# motor_Controller4.net
KiCad netlist of a schematic drawn in EAGLE
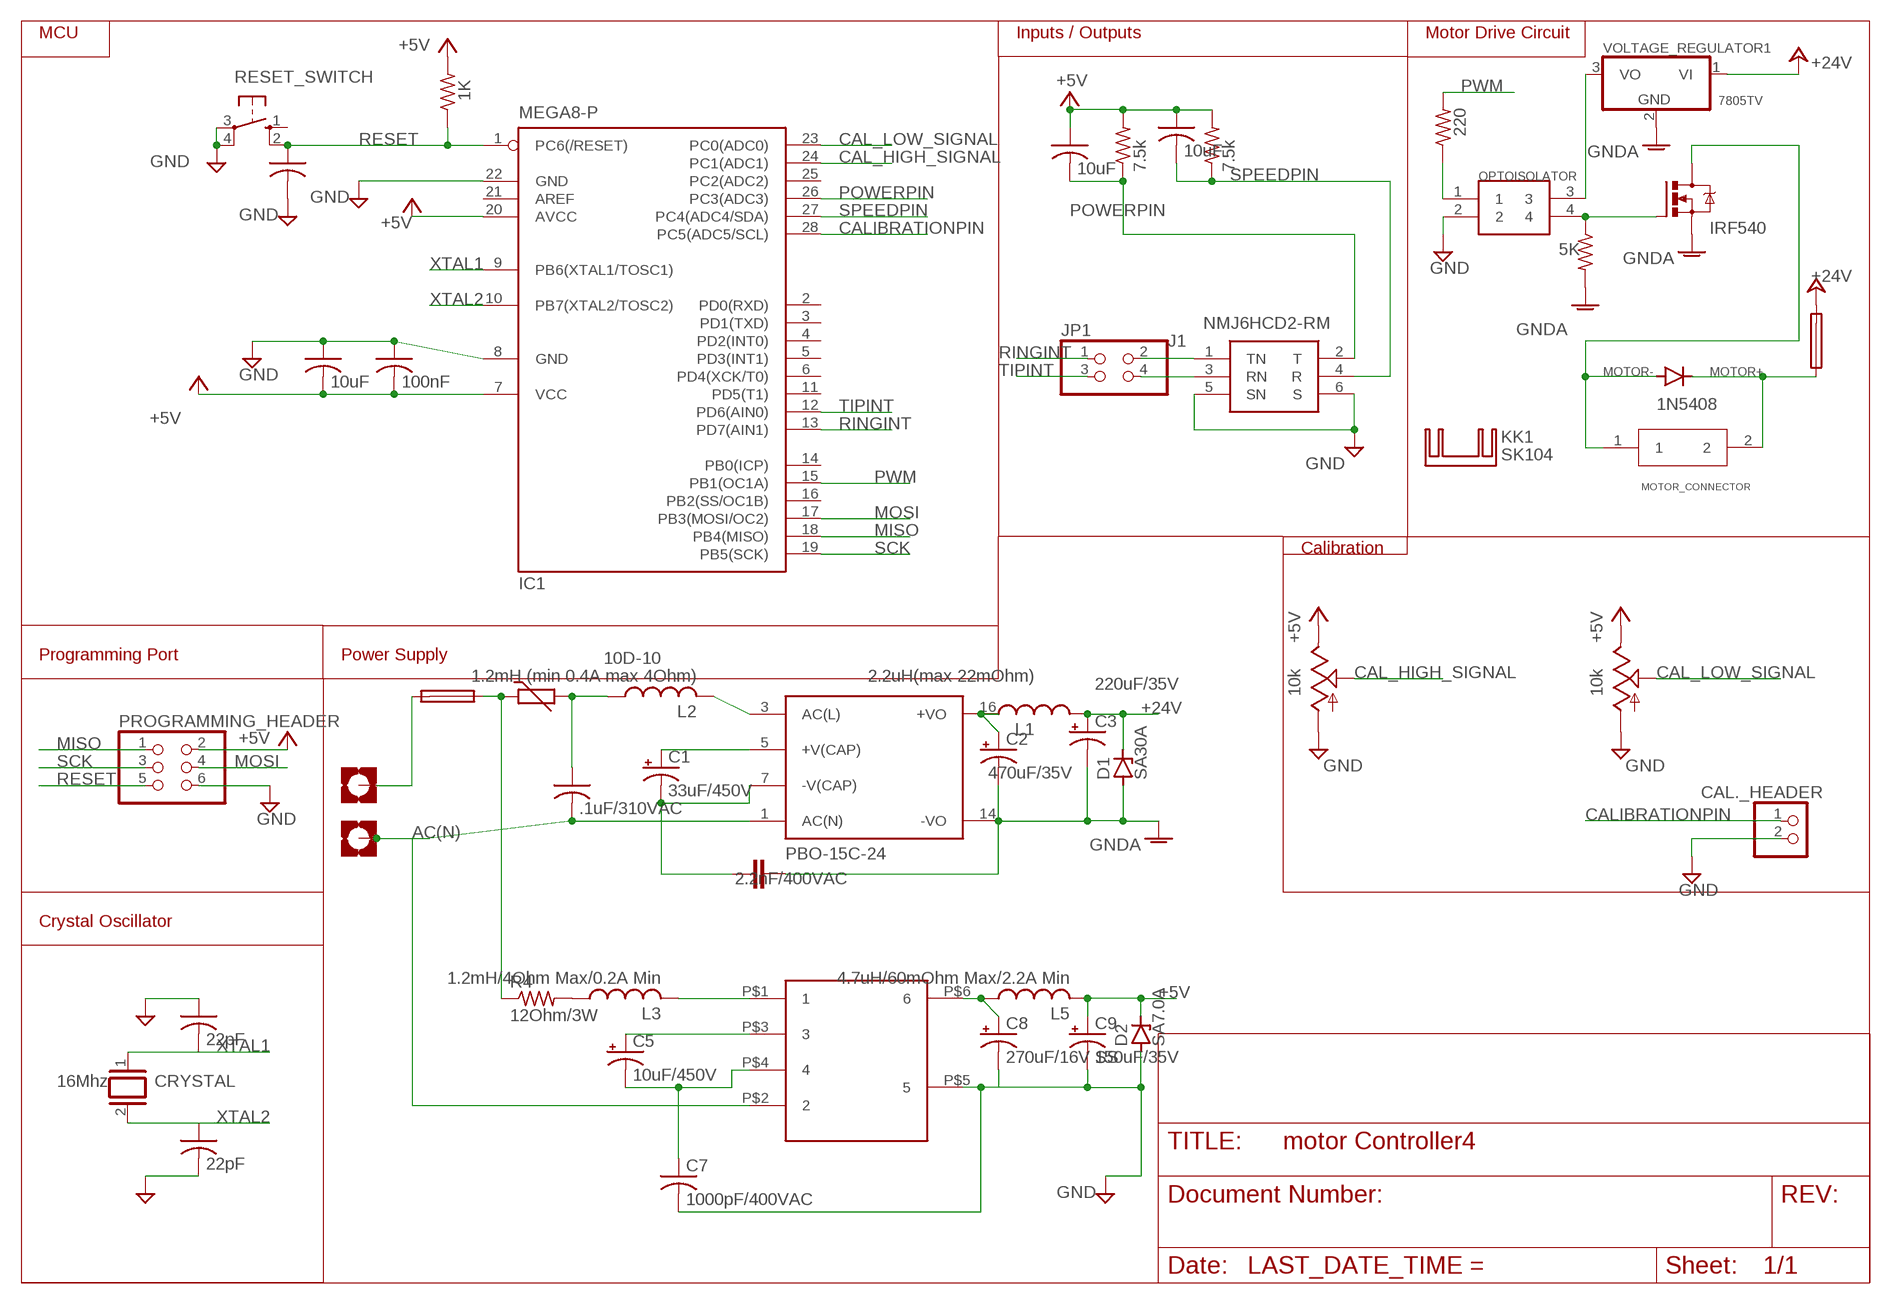
[diagram p0: schematic, sheet 1]

(export (version "E")
  (design (tool "Eeschema 10.0.6"))
  (components
    (comp (ref "1N5408")
      (value "1N5408")
      (footprint "eagle-import:DO201-15")
      (fields (field (name "MF") "VISHAY") (field (name "MPN") "1N5408-E3/54"))
      (libsource (lib "eagle-import") (part "1N5400"))
    )
    (comp (ref "C1")
      (value "33uF/450V")
      (footprint "eagle-import:E5-13")
      (libsource (lib "eagle-import") (part "CPOL-USE5-13"))
    )
    (comp (ref "C2")
      (value "470uF/35V")
      (footprint "eagle-import:E5-10,5")
      (fields (field (name "MF") "PANASONIC") (field (name "MPN") "ECA1VHG471B"))
      (libsource (lib "eagle-import") (part "CPOL-USE5-10.5"))
    )
    (comp (ref "C3")
      (value "220uF/35V")
      (footprint "eagle-import:E5-10,5")
      (fields (field (name "MF") "KEMET") (field (name "MPN") "A768KS227M1VLAE024"))
      (libsource (lib "eagle-import") (part "CPOL-USE5-10.5"))
    )
    (comp (ref "C4")
      (value ".1uF/310VAC")
      (footprint "eagle-import:C150-091X182")
      (libsource (lib "eagle-import") (part "C-US150-091X182"))
    )
    (comp (ref "C5")
      (value "10uF/450V")
      (footprint "eagle-import:E5-10,5")
      (libsource (lib "eagle-import") (part "CPOL-USE5-10.5"))
    )
    (comp (ref "C6")
      (value "22pF")
      (footprint "eagle-import:C025-024X044")
      (libsource (lib "eagle-import") (part "C-US025-024X044"))
    )
    (comp (ref "C7")
      (value "1000pF/400VAC")
      (footprint "eagle-import:C075-052X106")
      (libsource (lib "eagle-import") (part "C-US075-052X106"))
    )
    (comp (ref "C8")
      (value "270uF/16V SS")
      (footprint "eagle-import:E2,5-6")
      (libsource (lib "eagle-import") (part "CPOL-USE2.5-6"))
    )
    (comp (ref "C9")
      (value "150uF/35V")
      (footprint "eagle-import:E3,5-8")
      (libsource (lib "eagle-import") (part "CPOL-USE3.5-8"))
    )
    (comp (ref "C10")
      (value "10uF")
      (footprint "eagle-import:C025-024X044")
      (libsource (lib "eagle-import") (part "C-US025-024X044"))
    )
    (comp (ref "C11")
      (value "C-US025-024X044")
      (footprint "eagle-import:C025-024X044")
      (libsource (lib "eagle-import") (part "C-US025-024X044"))
    )
    (comp (ref "C12")
      (value "10uF")
      (footprint "eagle-import:C025-024X044")
      (libsource (lib "eagle-import") (part "C-US025-024X044"))
    )
    (comp (ref "C13")
      (value "10uF")
      (footprint "eagle-import:C025-024X044")
      (libsource (lib "eagle-import") (part "C-US025-024X044"))
    )
    (comp (ref "C14")
      (value "100nF")
      (footprint "eagle-import:C025-024X044")
      (libsource (lib "eagle-import") (part "C-US025-024X044"))
    )
    (comp (ref "C15")
      (value "22pF")
      (footprint "eagle-import:C025-024X044")
      (libsource (lib "eagle-import") (part "C-US025-024X044"))
    )
    (comp (ref "CAL._HEADER")
      (value "PINHD-1X2")
      (footprint "eagle-import:1X02")
      (libsource (lib "eagle-import") (part "PINHD-1X2"))
    )
    (comp (ref "CRYSTAL")
      (value "16Mhz")
      (footprint "eagle-import:QS")
      (libsource (lib "eagle-import") (part "XTAL/S"))
    )
    (comp (ref "CY1")
      (value "2.2nF/400VAC")
      (footprint "eagle-import:YC10B4")
      (libsource (lib "eagle-import") (part "CYYC10B4"))
    )
    (comp (ref "D1")
      (value "SA30A")
      (footprint "eagle-import:ZDIO-7.5")
      (libsource (lib "eagle-import") (part "ZENER-DIODEZD-7.5"))
    )
    (comp (ref "D2")
      (value "SA7.0A")
      (footprint "eagle-import:ZDIO-7.5")
      (libsource (lib "eagle-import") (part "ZENER-DIODEZD-7.5"))
    )
    (comp (ref "F1")
      (value "FUSESH22,5")
      (footprint "eagle-import:SH22,5")
      (libsource (lib "eagle-import") (part "FUSESH22,5"))
    )
    (comp (ref "F2")
      (value "1A/300V")
      (footprint "eagle-import:SH22,5")
      (libsource (lib "eagle-import") (part "FUSESH22,5"))
    )
    (comp (ref "FAST")
      (value "10k")
      (footprint "eagle-import:CT6")
      (libsource (lib "eagle-import") (part "TRIM_US-CT6"))
    )
    (comp (ref "H1")
      (value "MOUNT-PAD-SQUARE3.6")
      (footprint "eagle-import:3,6-PAD-SQUARE")
      (libsource (lib "eagle-import") (part "MOUNT-PAD-SQUARE3.6"))
    )
    (comp (ref "H2")
      (value "MOUNT-PAD-SQUARE3.6")
      (footprint "eagle-import:3,6-PAD-SQUARE")
      (libsource (lib "eagle-import") (part "MOUNT-PAD-SQUARE3.6"))
    )
    (comp (ref "IC1")
      (value "MEGA8-P")
      (footprint "eagle-import:DIL28-3")
      (libsource (lib "eagle-import") (part "MEGA8-P"))
    )
    (comp (ref "J1")
      (value "NMJ6HCD2-RM")
      (footprint "eagle-import:NMJ6HCD2RM")
      (fields (field (name "MOUSER_PART_NUMBER") "568-NMJ6HCD2-RM"))
      (libsource (lib "eagle-import") (part "NMJ6HCD2-RM"))
    )
    (comp (ref "JP1")
      (value "PINHD-2X2")
      (footprint "eagle-import:2X02")
      (libsource (lib "eagle-import") (part "PINHD-2X2"))
    )
    (comp (ref "KK1")
      (value "SK104")
      (footprint "eagle-import:SK104")
      (libsource (lib "eagle-import") (part "SK104"))
    )
    (comp (ref "L1")
      (value "2.2uH(max 22mOhm)")
      (footprint "eagle-import:TJ5-U1")
      (libsource (lib "eagle-import") (part "L-USTJ5-U1"))
    )
    (comp (ref "L2")
      (value "1.2mH (min 0.4A max 4Ohm)")
      (footprint "eagle-import:6000-XXXX-RC")
      (libsource (lib "eagle-import") (part "L-US6000-XXX-RC"))
    )
    (comp (ref "L3")
      (value "1.2mH/4Ohm Max/0.2A Min")
      (footprint "eagle-import:6000-XXXX-RC")
      (libsource (lib "eagle-import") (part "L-US6000-XXX-RC"))
    )
    (comp (ref "L5")
      (value "4.7uH/60mOhm Max/2.2A Min")
      (footprint "eagle-import:0207_2V")
      (libsource (lib "eagle-import") (part "L-US0207/2V"))
    )
    (comp (ref "MOTOR_CONNECTOR")
      (value "641963-1")
      (footprint "eagle-import:641963-1_TYC")
      (libsource (lib "eagle-import") (part "641963-1"))
    )
    (comp (ref "OPTOISOLATOR")
      (value "SFH619A")
      (footprint "eagle-import:SFH619A")
      (fields (field (name "OPTOISOLATOR") "SFH619A"))
      (libsource (lib "eagle-import") (part "SFH619A-ND"))
    )
    (comp (ref "PROGRAMMING_HEADER")
      (value "PINHD-2X3")
      (footprint "eagle-import:2X03")
      (libsource (lib "eagle-import") (part "PINHD-2X3"))
    )
    (comp (ref "PS1")
      (value "PBO-15C-24")
      (footprint "eagle-import:CONV_PBO-15C-24")
      (fields (field (name "MF") "CUI Inc."))
      (libsource (lib "eagle-import") (part "PBO-15C-24"))
    )
    (comp (ref "Q1")
      (value "IRF540")
      (footprint "eagle-import:TO220BV")
      (libsource (lib "eagle-import") (part "IRF540"))
    )
    (comp (ref "R1")
      (value "10D-10")
      (footprint "eagle-import:R-7,5")
      (libsource (lib "eagle-import") (part "THERMISTOR-7,5"))
    )
    (comp (ref "R2")
      (value "1K")
      (footprint "eagle-import:0204_7")
      (libsource (lib "eagle-import") (part "R-US_0204/7"))
    )
    (comp (ref "R3")
      (value "7.5k")
      (footprint "eagle-import:0204_7")
      (libsource (lib "eagle-import") (part "R-US_0204/7"))
    )
    (comp (ref "R4")
      (value "12Ohm/3W")
      (footprint "eagle-import:0617_22")
      (libsource (lib "eagle-import") (part "R-US_0617/22"))
    )
    (comp (ref "R5")
      (value "220")
      (footprint "eagle-import:0204_7")
      (libsource (lib "eagle-import") (part "R-US_0204/7"))
    )
    (comp (ref "R6")
      (value "5K")
      (footprint "eagle-import:0204_7")
      (libsource (lib "eagle-import") (part "R-US_0204/7"))
    )
    (comp (ref "R7")
      (value "7.5k")
      (footprint "eagle-import:0204_7")
      (libsource (lib "eagle-import") (part "R-US_0204/7"))
    )
    (comp (ref "RESET_SWITCH")
      (value "10-XX")
      (footprint "eagle-import:B3F-10XX")
      (fields (field (name "MPN") "B3F-1000") (field (name "OC_NEWARK") "unknown"))
      (libsource (lib "eagle-import") (part "10-XX"))
    )
    (comp (ref "SLOW")
      (value "10k")
      (footprint "eagle-import:CT6")
      (libsource (lib "eagle-import") (part "TRIM_US-CT6"))
    )
    (comp (ref "U$1")
      (value "L503-13B05R$3")
      (footprint "eagle-import:LS03-13BO5R3")
      (libsource (lib "eagle-import") (part "L503-13B05R$3"))
    )
    (comp (ref "VOLTAGE_REGULATOR1")
      (value "7805TV")
      (footprint "eagle-import:TO220V")
      (libsource (lib "eagle-import") (part "78TV05"))
    )
  )
  (nets
    (net (code "1") (name "+5V") (class "Default")
      (node (ref "C10") (pin "1") (pinfunction "1_1") (pintype "passive"))
      (node (ref "C12") (pin "1") (pinfunction "1_1") (pintype "passive"))
      (node (ref "C13") (pin "2") (pinfunction "2_2") (pintype "passive"))
      (node (ref "C14") (pin "2") (pinfunction "2_2") (pintype "passive"))
      (node (ref "C9") (pin "+") (pinfunction "+_+") (pintype "passive"))
      (node (ref "D2") (pin "C") (pinfunction "C_C") (pintype "passive"))
      (node (ref "FAST") (pin "E") (pinfunction "E_E") (pintype "passive"))
      (node (ref "IC1") (pin "20") (pinfunction "AVCC_20") (pintype "power_in"))
      (node (ref "IC1") (pin "7") (pinfunction "VCC_7") (pintype "power_in"))
      (node (ref "L5") (pin "2") (pinfunction "2_2") (pintype "passive"))
      (node (ref "PROGRAMMING_HEADER") (pin "2") (pinfunction "2_2") (pintype "passive"))
      (node (ref "R2") (pin "2") (pinfunction "2_2") (pintype "passive"))
      (node (ref "R3") (pin "2") (pinfunction "2_2") (pintype "passive"))
      (node (ref "R7") (pin "2") (pinfunction "2_2") (pintype "passive"))
      (node (ref "SLOW") (pin "E") (pinfunction "E_E") (pintype "passive"))
    )
    (net (code "2") (name "+24V") (class "Default")
      (node (ref "C3") (pin "+") (pinfunction "+_+") (pintype "passive"))
      (node (ref "D1") (pin "C") (pinfunction "C_C") (pintype "passive"))
      (node (ref "F1") (pin "2") (pinfunction "2_2") (pintype "passive"))
      (node (ref "L1") (pin "2") (pinfunction "2_2") (pintype "passive"))
      (node (ref "VOLTAGE_REGULATOR1") (pin "1") (pinfunction "VI_1") (pintype "input"))
    )
    (net (code "3") (name "/AC(N)") (class "Default")
      (node (ref "C4") (pin "2") (pinfunction "2_2") (pintype "passive"))
      (node (ref "H2") (pin "B3,6") (pinfunction "MOUNT_B3,6") (pintype "passive"))
      (node (ref "PS1") (pin "1") (pinfunction "AC(N)_1") (pintype "input"))
      (node (ref "U$1") (pin "P$2") (pinfunction "2_P$2") (pintype "bidirectional"))
    )
    (net (code "4") (name "/CALIBRATIONPIN") (class "Default")
      (node (ref "CAL._HEADER") (pin "1") (pinfunction "1_1") (pintype "passive"))
      (node (ref "IC1") (pin "28") (pinfunction "PC5(ADC5/SCL)_28") (pintype "bidirectional"))
    )
    (net (code "5") (name "/CAL_HIGH_SIGNAL") (class "Default")
      (node (ref "FAST") (pin "S") (pinfunction "S_S") (pintype "passive"))
      (node (ref "IC1") (pin "24") (pinfunction "PC1(ADC1)_24") (pintype "bidirectional"))
    )
    (net (code "6") (name "/CAL_LOW_SIGNAL") (class "Default")
      (node (ref "IC1") (pin "23") (pinfunction "PC0(ADC0)_23") (pintype "bidirectional"))
      (node (ref "SLOW") (pin "S") (pinfunction "S_S") (pintype "passive"))
    )
    (net (code "7") (name "/MISO") (class "Default")
      (node (ref "IC1") (pin "18") (pinfunction "PB4(MISO)_18") (pintype "bidirectional"))
      (node (ref "PROGRAMMING_HEADER") (pin "1") (pinfunction "1_1") (pintype "passive"))
    )
    (net (code "8") (name "/MOSI") (class "Default")
      (node (ref "IC1") (pin "17") (pinfunction "PB3(MOSI/OC2)_17") (pintype "bidirectional"))
      (node (ref "PROGRAMMING_HEADER") (pin "4") (pinfunction "4_4") (pintype "passive"))
    )
    (net (code "9") (name "/MOTOR+") (class "Default")
      (node (ref "1N5408") (pin "C") (pinfunction "C_C") (pintype "passive"))
      (node (ref "F1") (pin "1") (pinfunction "1_1") (pintype "passive"))
      (node (ref "MOTOR_CONNECTOR") (pin "2") (pinfunction "2_2") (pintype "passive"))
    )
    (net (code "10") (name "/MOTOR-") (class "Default")
      (node (ref "1N5408") (pin "A") (pinfunction "A_A") (pintype "passive"))
      (node (ref "MOTOR_CONNECTOR") (pin "1") (pinfunction "1_1") (pintype "passive"))
      (node (ref "Q1") (pin "D") (pinfunction "D_D") (pintype "passive"))
    )
    (net (code "11") (name "/POWERPIN") (class "Default")
      (node (ref "C10") (pin "2") (pinfunction "2_2") (pintype "passive"))
      (node (ref "IC1") (pin "26") (pinfunction "PC3(ADC3)_26") (pintype "bidirectional"))
      (node (ref "J1") (pin "2") (pinfunction "T_2") (pintype "bidirectional"))
      (node (ref "R3") (pin "1") (pinfunction "1_1") (pintype "passive"))
    )
    (net (code "12") (name "/PWM") (class "Default")
      (node (ref "IC1") (pin "15") (pinfunction "PB1(OC1A)_15") (pintype "bidirectional"))
      (node (ref "R5") (pin "2") (pinfunction "2_2") (pintype "passive"))
    )
    (net (code "13") (name "/RESET") (class "Default")
      (node (ref "C11") (pin "1") (pinfunction "1_1") (pintype "passive"))
      (node (ref "IC1") (pin "1") (pinfunction "PC6(/RESET)_1") (pintype "bidirectional"))
      (node (ref "PROGRAMMING_HEADER") (pin "5") (pinfunction "5_5") (pintype "passive"))
      (node (ref "R2") (pin "1") (pinfunction "1_1") (pintype "passive"))
      (node (ref "RESET_SWITCH") (pin "2") (pinfunction "S1_2") (pintype "passive"))
    )
    (net (code "14") (name "/RINGINT") (class "Default")
      (node (ref "IC1") (pin "13") (pinfunction "PD7(AIN1)_13") (pintype "bidirectional"))
      (node (ref "JP1") (pin "1") (pinfunction "1_1") (pintype "passive"))
    )
    (net (code "15") (name "/SCK") (class "Default")
      (node (ref "IC1") (pin "19") (pinfunction "PB5(SCK)_19") (pintype "bidirectional"))
      (node (ref "PROGRAMMING_HEADER") (pin "3") (pinfunction "3_3") (pintype "passive"))
    )
    (net (code "16") (name "/SPEEDPIN") (class "Default")
      (node (ref "C12") (pin "2") (pinfunction "2_2") (pintype "passive"))
      (node (ref "IC1") (pin "27") (pinfunction "PC4(ADC4/SDA)_27") (pintype "bidirectional"))
      (node (ref "J1") (pin "4") (pinfunction "R_4") (pintype "bidirectional"))
      (node (ref "R7") (pin "1") (pinfunction "1_1") (pintype "passive"))
    )
    (net (code "17") (name "/TIPINT") (class "Default")
      (node (ref "IC1") (pin "12") (pinfunction "PD6(AIN0)_12") (pintype "bidirectional"))
      (node (ref "JP1") (pin "3") (pinfunction "3_3") (pintype "passive"))
    )
    (net (code "18") (name "/XTAL1") (class "Default")
      (node (ref "C15") (pin "2") (pinfunction "2_2") (pintype "passive"))
      (node (ref "CRYSTAL") (pin "1") (pinfunction "1_1") (pintype "passive"))
      (node (ref "IC1") (pin "9") (pinfunction "PB6(XTAL1/TOSC1)_9") (pintype "bidirectional"))
    )
    (net (code "19") (name "/XTAL2") (class "Default")
      (node (ref "C6") (pin "1") (pinfunction "1_1") (pintype "passive"))
      (node (ref "CRYSTAL") (pin "2") (pinfunction "2_2") (pintype "passive"))
      (node (ref "IC1") (pin "10") (pinfunction "PB7(XTAL2/TOSC2)_10") (pintype "bidirectional"))
    )
    (net (code "20") (name "GND") (class "Default")
      (node (ref "C11") (pin "2") (pinfunction "2_2") (pintype "passive"))
      (node (ref "C13") (pin "1") (pinfunction "1_1") (pintype "passive"))
      (node (ref "C14") (pin "1") (pinfunction "1_1") (pintype "passive"))
      (node (ref "C15") (pin "1") (pinfunction "1_1") (pintype "passive"))
      (node (ref "C6") (pin "2") (pinfunction "2_2") (pintype "passive"))
      (node (ref "C7") (pin "2") (pinfunction "2_2") (pintype "passive"))
      (node (ref "C8") (pin "-") (pinfunction "-_-") (pintype "passive"))
      (node (ref "C9") (pin "-") (pinfunction "-_-") (pintype "passive"))
      (node (ref "CAL._HEADER") (pin "2") (pinfunction "2_2") (pintype "passive"))
      (node (ref "D2") (pin "A") (pinfunction "A_A") (pintype "passive"))
      (node (ref "FAST") (pin "A") (pinfunction "A_A") (pintype "passive"))
      (node (ref "IC1") (pin "22") (pinfunction "GND_22") (pintype "power_in"))
      (node (ref "IC1") (pin "8") (pinfunction "GND_8") (pintype "power_in"))
      (node (ref "J1") (pin "5") (pinfunction "SN_5") (pintype "bidirectional"))
      (node (ref "J1") (pin "6") (pinfunction "S_6") (pintype "bidirectional"))
      (node (ref "OPTOISOLATOR") (pin "2") (pinfunction "2_2") (pintype "bidirectional"))
      (node (ref "PROGRAMMING_HEADER") (pin "6") (pinfunction "6_6") (pintype "passive"))
      (node (ref "RESET_SWITCH") (pin "3") (pinfunction "P_3") (pintype "passive"))
      (node (ref "RESET_SWITCH") (pin "4") (pinfunction "P1_4") (pintype "passive"))
      (node (ref "SLOW") (pin "A") (pinfunction "A_A") (pintype "passive"))
      (node (ref "U$1") (pin "P$5") (pinfunction "5_P$5") (pintype "bidirectional"))
    )
    (net (code "21") (name "GNDA") (class "Default")
      (node (ref "C2") (pin "-") (pinfunction "-_-") (pintype "passive"))
      (node (ref "C3") (pin "-") (pinfunction "-_-") (pintype "passive"))
      (node (ref "CY1") (pin "1") (pinfunction "1_1") (pintype "passive"))
      (node (ref "D1") (pin "A") (pinfunction "A_A") (pintype "passive"))
      (node (ref "PS1") (pin "14") (pinfunction "-VO_14") (pintype "output"))
      (node (ref "Q1") (pin "S") (pinfunction "S_S") (pintype "passive"))
      (node (ref "R6") (pin "2") (pinfunction "2_2") (pintype "passive"))
      (node (ref "VOLTAGE_REGULATOR1") (pin "2") (pinfunction "GND_2") (pintype "passive"))
    )
    (net (code "22") (name "Net-(C4-Pad1)") (class "Default")
      (node (ref "C4") (pin "1") (pinfunction "1_1") (pintype "passive"))
      (node (ref "L2") (pin "1") (pinfunction "1_1") (pintype "passive"))
      (node (ref "R1") (pin "2") (pinfunction "2_2") (pintype "passive"))
    )
    (net (code "23") (name "Net-(F2-Pad1)") (class "Default")
      (node (ref "F2") (pin "1") (pinfunction "1_1") (pintype "passive"))
      (node (ref "R1") (pin "1") (pinfunction "1_1") (pintype "passive"))
      (node (ref "R4") (pin "1") (pinfunction "1_1") (pintype "passive"))
    )
    (net (code "24") (name "Net-(H1-MOUNT)") (class "Default")
      (node (ref "F2") (pin "2") (pinfunction "2_2") (pintype "passive"))
      (node (ref "H1") (pin "B3,6") (pinfunction "MOUNT_B3,6") (pintype "passive"))
    )
    (net (code "25") (name "Net-(J1-RN)") (class "Default")
      (node (ref "J1") (pin "3") (pinfunction "RN_3") (pintype "bidirectional"))
      (node (ref "JP1") (pin "4") (pinfunction "4_4") (pintype "passive"))
    )
    (net (code "26") (name "Net-(J1-TN)") (class "Default")
      (node (ref "J1") (pin "1") (pinfunction "TN_1") (pintype "bidirectional"))
      (node (ref "JP1") (pin "2") (pinfunction "2_2") (pintype "passive"))
    )
    (net (code "27") (name "Net-(L3-Pad1)") (class "Default")
      (node (ref "L3") (pin "1") (pinfunction "1_1") (pintype "passive"))
      (node (ref "R4") (pin "2") (pinfunction "2_2") (pintype "passive"))
    )
    (net (code "28") (name "Net-(OPTOISOLATOR-Pad1)") (class "Default")
      (node (ref "OPTOISOLATOR") (pin "1") (pinfunction "1_1") (pintype "bidirectional"))
      (node (ref "R5") (pin "1") (pinfunction "1_1") (pintype "passive"))
    )
    (net (code "29") (name "Net-(OPTOISOLATOR-Pad4)") (class "Default")
      (node (ref "OPTOISOLATOR") (pin "4") (pinfunction "4_4") (pintype "bidirectional"))
      (node (ref "Q1") (pin "G") (pinfunction "G_G") (pintype "passive"))
      (node (ref "R6") (pin "1") (pinfunction "1_1") (pintype "passive"))
    )
    (net (code "30") (name "Net-(PS1-+V(CAP))") (class "Default")
      (node (ref "C1") (pin "+") (pinfunction "+_+") (pintype "passive"))
      (node (ref "PS1") (pin "5") (pinfunction "+V(CAP)_5") (pintype "passive"))
    )
    (net (code "31") (name "Net-(PS1-+VO)") (class "Default")
      (node (ref "C2") (pin "+") (pinfunction "+_+") (pintype "passive"))
      (node (ref "L1") (pin "1") (pinfunction "1_1") (pintype "passive"))
      (node (ref "PS1") (pin "16") (pinfunction "+VO_16") (pintype "output"))
    )
    (net (code "32") (name "Net-(PS1--V(CAP))") (class "Default")
      (node (ref "C1") (pin "-") (pinfunction "-_-") (pintype "passive"))
      (node (ref "CY1") (pin "2") (pinfunction "2_2") (pintype "passive"))
      (node (ref "PS1") (pin "7") (pinfunction "-V(CAP)_7") (pintype "passive"))
    )
    (net (code "33") (name "Net-(PS1-AC(L))") (class "Default")
      (node (ref "L2") (pin "2") (pinfunction "2_2") (pintype "passive"))
      (node (ref "PS1") (pin "3") (pinfunction "AC(L)_3") (pintype "input"))
    )
    (net (code "34") (name "Net-(U$1-1)") (class "Default")
      (node (ref "L3") (pin "2") (pinfunction "2_2") (pintype "passive"))
      (node (ref "U$1") (pin "P$1") (pinfunction "1_P$1") (pintype "bidirectional"))
    )
    (net (code "35") (name "Net-(U$1-3)") (class "Default")
      (node (ref "C5") (pin "+") (pinfunction "+_+") (pintype "passive"))
      (node (ref "U$1") (pin "P$3") (pinfunction "3_P$3") (pintype "bidirectional"))
    )
    (net (code "36") (name "Net-(U$1-4)") (class "Default")
      (node (ref "C5") (pin "-") (pinfunction "-_-") (pintype "passive"))
      (node (ref "C7") (pin "1") (pinfunction "1_1") (pintype "passive"))
      (node (ref "U$1") (pin "P$4") (pinfunction "4_P$4") (pintype "bidirectional"))
    )
    (net (code "37") (name "Net-(U$1-6)") (class "Default")
      (node (ref "C8") (pin "+") (pinfunction "+_+") (pintype "passive"))
      (node (ref "L5") (pin "1") (pinfunction "1_1") (pintype "passive"))
      (node (ref "U$1") (pin "P$6") (pinfunction "6_P$6") (pintype "bidirectional"))
    )
    (net (code "38") (name "Net-(VOLTAGE_REGULATOR1-VO)") (class "Default")
      (node (ref "OPTOISOLATOR") (pin "3") (pinfunction "3_3") (pintype "bidirectional"))
      (node (ref "VOLTAGE_REGULATOR1") (pin "3") (pinfunction "VO_3") (pintype "passive"))
    )
    (net (code "39") (name "unconnected-(IC1-AREF-Pad21)") (class "Default")
      (node (ref "IC1") (pin "21") (pinfunction "AREF_21") (pintype "passive"))
    )
    (net (code "40") (name "unconnected-(IC1-PB0(ICP)-Pad14)") (class "Default")
      (node (ref "IC1") (pin "14") (pinfunction "PB0(ICP)_14") (pintype "bidirectional"))
    )
    (net (code "41") (name "unconnected-(IC1-PB2(SS{slash}OC1B)-Pad16)") (class "Default")
      (node (ref "IC1") (pin "16") (pinfunction "PB2(SS/OC1B)_16") (pintype "bidirectional"))
    )
    (net (code "42") (name "unconnected-(IC1-PC2(ADC2)-Pad25)") (class "Default")
      (node (ref "IC1") (pin "25") (pinfunction "PC2(ADC2)_25") (pintype "bidirectional"))
    )
    (net (code "43") (name "unconnected-(IC1-PD0(RXD)-Pad2)") (class "Default")
      (node (ref "IC1") (pin "2") (pinfunction "PD0(RXD)_2") (pintype "bidirectional"))
    )
    (net (code "44") (name "unconnected-(IC1-PD1(TXD)-Pad3)") (class "Default")
      (node (ref "IC1") (pin "3") (pinfunction "PD1(TXD)_3") (pintype "bidirectional"))
    )
    (net (code "45") (name "unconnected-(IC1-PD2(INT0)-Pad4)") (class "Default")
      (node (ref "IC1") (pin "4") (pinfunction "PD2(INT0)_4") (pintype "bidirectional"))
    )
    (net (code "46") (name "unconnected-(IC1-PD3(INT1)-Pad5)") (class "Default")
      (node (ref "IC1") (pin "5") (pinfunction "PD3(INT1)_5") (pintype "bidirectional"))
    )
    (net (code "47") (name "unconnected-(IC1-PD4(XCK{slash}T0)-Pad6)") (class "Default")
      (node (ref "IC1") (pin "6") (pinfunction "PD4(XCK/T0)_6") (pintype "bidirectional"))
    )
    (net (code "48") (name "unconnected-(IC1-PD5(T1)-Pad11)") (class "Default")
      (node (ref "IC1") (pin "11") (pinfunction "PD5(T1)_11") (pintype "bidirectional"))
    )
    (net (code "49") (name "unconnected-(RESET_SWITCH-S-Pad1)") (class "Default")
      (node (ref "RESET_SWITCH") (pin "1") (pinfunction "S_1") (pintype "passive"))
    )
  )
)
